# DDR5_System_Connector.net
KiCad netlist of a schematic drawn in Altium Designer
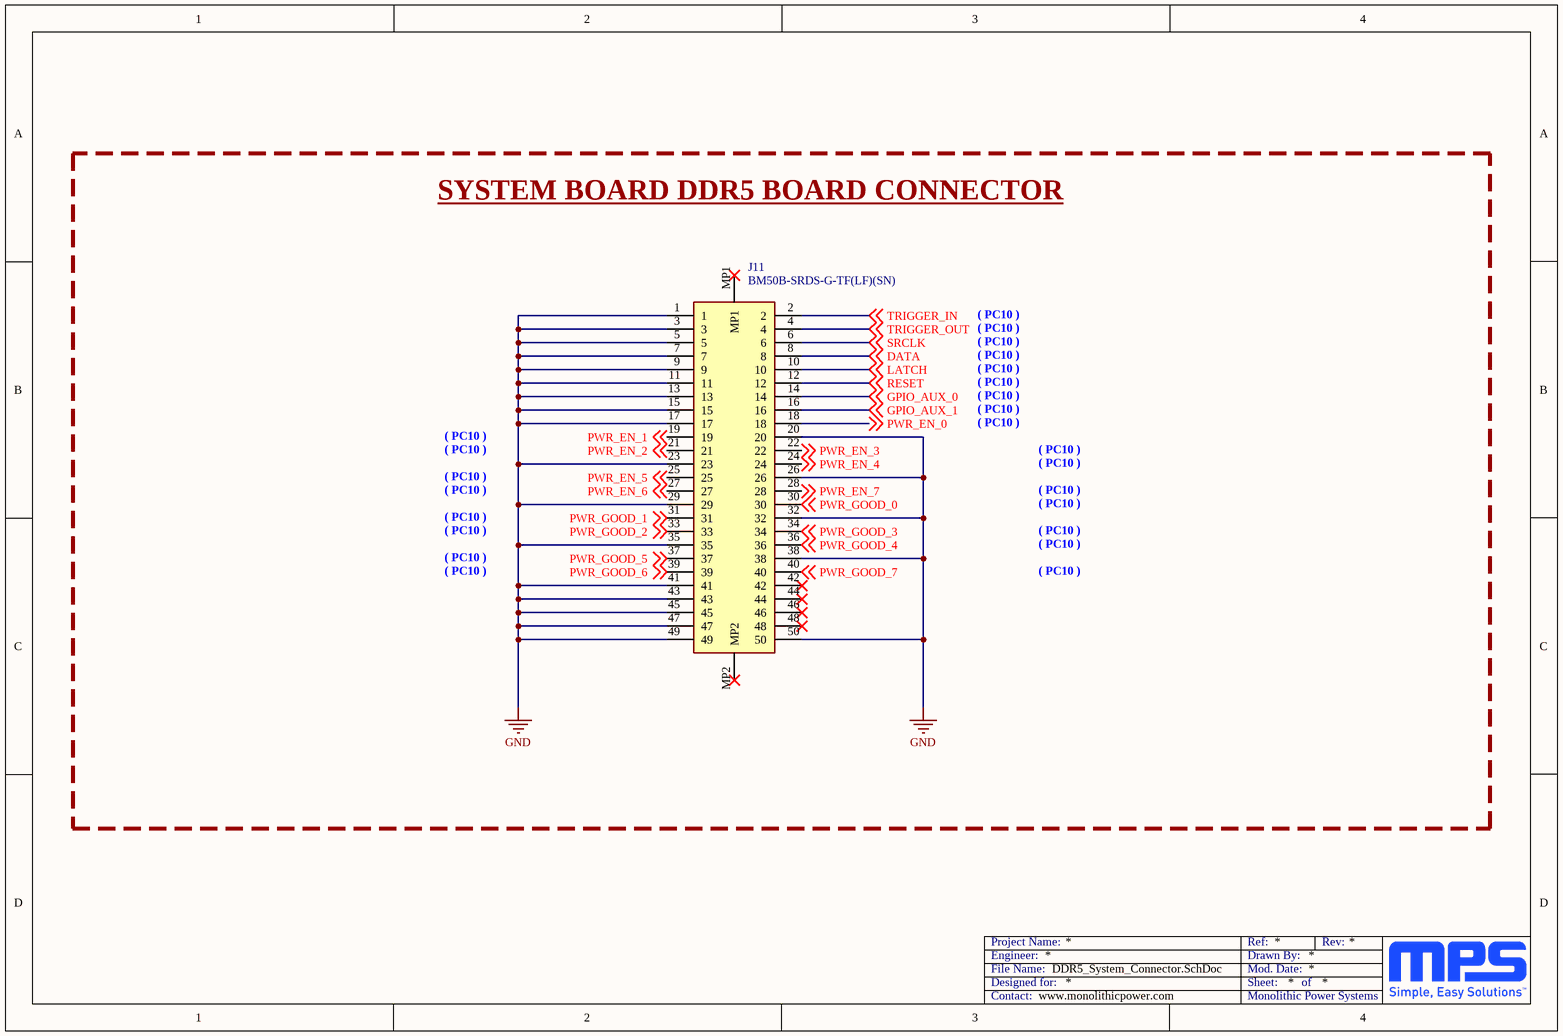
[diagram p0: DDR5_System_Connector.SchDoc]

(export (version "E")
  (design (tool "Eeschema 10.0.6"))
  (components
    (comp (ref "J11")
      (value "BM50B-SRDS-G-TF(LF)(SN)")
      (footprint "BM50BSRDSGTFLFSN")
      (fields (field (name "MANUFACTURER") "JST"))
      (libsource (lib "DDR5_Nucleo_Shield_Symbols") (part "BM50B-SRDS-G-TF(LF)(SN)"))
    )
  )
  (nets
    (net (code "1") (name "DATA") (class "Default")
      (node (ref "J11") (pin "8") (pinfunction "8_8") (pintype "passive"))
    )
    (net (code "2") (name "GND") (class "Default")
      (node (ref "J11") (pin "1") (pinfunction "1_1") (pintype "passive"))
      (node (ref "J11") (pin "11") (pinfunction "11_11") (pintype "passive"))
      (node (ref "J11") (pin "13") (pinfunction "13_13") (pintype "passive"))
      (node (ref "J11") (pin "15") (pinfunction "15_15") (pintype "passive"))
      (node (ref "J11") (pin "17") (pinfunction "17_17") (pintype "passive"))
      (node (ref "J11") (pin "20") (pinfunction "20_20") (pintype "passive"))
      (node (ref "J11") (pin "23") (pinfunction "23_23") (pintype "passive"))
      (node (ref "J11") (pin "26") (pinfunction "26_26") (pintype "passive"))
      (node (ref "J11") (pin "29") (pinfunction "29_29") (pintype "passive"))
      (node (ref "J11") (pin "3") (pinfunction "3_3") (pintype "passive"))
      (node (ref "J11") (pin "32") (pinfunction "32_32") (pintype "passive"))
      (node (ref "J11") (pin "35") (pinfunction "35_35") (pintype "passive"))
      (node (ref "J11") (pin "38") (pinfunction "38_38") (pintype "passive"))
      (node (ref "J11") (pin "41") (pinfunction "41_41") (pintype "passive"))
      (node (ref "J11") (pin "43") (pinfunction "43_43") (pintype "passive"))
      (node (ref "J11") (pin "45") (pinfunction "45_45") (pintype "passive"))
      (node (ref "J11") (pin "47") (pinfunction "47_47") (pintype "passive"))
      (node (ref "J11") (pin "49") (pinfunction "49_49") (pintype "passive"))
      (node (ref "J11") (pin "5") (pinfunction "5_5") (pintype "passive"))
      (node (ref "J11") (pin "50") (pinfunction "50_50") (pintype "passive"))
      (node (ref "J11") (pin "7") (pinfunction "7_7") (pintype "passive"))
      (node (ref "J11") (pin "9") (pinfunction "9_9") (pintype "passive"))
    )
    (net (code "3") (name "GPIO_AUX_0") (class "Default")
      (node (ref "J11") (pin "14") (pinfunction "14_14") (pintype "passive"))
    )
    (net (code "4") (name "GPIO_AUX_1") (class "Default")
      (node (ref "J11") (pin "16") (pinfunction "16_16") (pintype "passive"))
    )
    (net (code "5") (name "LATCH") (class "Default")
      (node (ref "J11") (pin "10") (pinfunction "10_10") (pintype "passive"))
    )
    (net (code "6") (name "PWR_EN_0") (class "Default")
      (node (ref "J11") (pin "18") (pinfunction "18_18") (pintype "passive"))
    )
    (net (code "7") (name "PWR_EN_1") (class "Default")
      (node (ref "J11") (pin "19") (pinfunction "19_19") (pintype "passive"))
    )
    (net (code "8") (name "PWR_EN_2") (class "Default")
      (node (ref "J11") (pin "21") (pinfunction "21_21") (pintype "passive"))
    )
    (net (code "9") (name "PWR_EN_3") (class "Default")
      (node (ref "J11") (pin "22") (pinfunction "22_22") (pintype "passive"))
    )
    (net (code "10") (name "PWR_EN_4") (class "Default")
      (node (ref "J11") (pin "24") (pinfunction "24_24") (pintype "passive"))
    )
    (net (code "11") (name "PWR_EN_5") (class "Default")
      (node (ref "J11") (pin "25") (pinfunction "25_25") (pintype "passive"))
    )
    (net (code "12") (name "PWR_EN_6") (class "Default")
      (node (ref "J11") (pin "27") (pinfunction "27_27") (pintype "passive"))
    )
    (net (code "13") (name "PWR_EN_7") (class "Default")
      (node (ref "J11") (pin "28") (pinfunction "28_28") (pintype "passive"))
    )
    (net (code "14") (name "PWR_GOOD_0") (class "Default")
      (node (ref "J11") (pin "30") (pinfunction "30_30") (pintype "passive"))
    )
    (net (code "15") (name "PWR_GOOD_1") (class "Default")
      (node (ref "J11") (pin "31") (pinfunction "31_31") (pintype "passive"))
    )
    (net (code "16") (name "PWR_GOOD_2") (class "Default")
      (node (ref "J11") (pin "33") (pinfunction "33_33") (pintype "passive"))
    )
    (net (code "17") (name "PWR_GOOD_3") (class "Default")
      (node (ref "J11") (pin "34") (pinfunction "34_34") (pintype "passive"))
    )
    (net (code "18") (name "PWR_GOOD_4") (class "Default")
      (node (ref "J11") (pin "36") (pinfunction "36_36") (pintype "passive"))
    )
    (net (code "19") (name "PWR_GOOD_5") (class "Default")
      (node (ref "J11") (pin "37") (pinfunction "37_37") (pintype "passive"))
    )
    (net (code "20") (name "PWR_GOOD_6") (class "Default")
      (node (ref "J11") (pin "39") (pinfunction "39_39") (pintype "passive"))
    )
    (net (code "21") (name "PWR_GOOD_7") (class "Default")
      (node (ref "J11") (pin "40") (pinfunction "40_40") (pintype "passive"))
    )
    (net (code "22") (name "RESET") (class "Default")
      (node (ref "J11") (pin "12") (pinfunction "12_12") (pintype "passive"))
    )
    (net (code "23") (name "SRCLK") (class "Default")
      (node (ref "J11") (pin "6") (pinfunction "6_6") (pintype "passive"))
    )
    (net (code "24") (name "TRIGGER_IN") (class "Default")
      (node (ref "J11") (pin "2") (pinfunction "2_2") (pintype "passive"))
    )
    (net (code "25") (name "TRIGGER_OUT") (class "Default")
      (node (ref "J11") (pin "4") (pinfunction "4_4") (pintype "passive"))
    )
    (net (code "26") (name "unconnected-(J11-Pad42)") (class "Default")
      (node (ref "J11") (pin "42") (pinfunction "42_42") (pintype "passive+no_connect"))
    )
    (net (code "27") (name "unconnected-(J11-Pad44)") (class "Default")
      (node (ref "J11") (pin "44") (pinfunction "44_44") (pintype "passive+no_connect"))
    )
    (net (code "28") (name "unconnected-(J11-Pad46)") (class "Default")
      (node (ref "J11") (pin "46") (pinfunction "46_46") (pintype "passive+no_connect"))
    )
    (net (code "29") (name "unconnected-(J11-Pad48)") (class "Default")
      (node (ref "J11") (pin "48") (pinfunction "48_48") (pintype "passive+no_connect"))
    )
    (net (code "30") (name "unconnected-(J11-PadMP1)") (class "Default")
      (node (ref "J11") (pin "MP1") (pinfunction "MP1_MP1") (pintype "passive+no_connect"))
    )
    (net (code "31") (name "unconnected-(J11-PadMP2)") (class "Default")
      (node (ref "J11") (pin "MP2") (pinfunction "MP2_MP2") (pintype "passive+no_connect"))
    )
  )
)
